# PB2_AdapterBoard_Rev0.net
KiCad netlist of a schematic drawn in Altium Designer
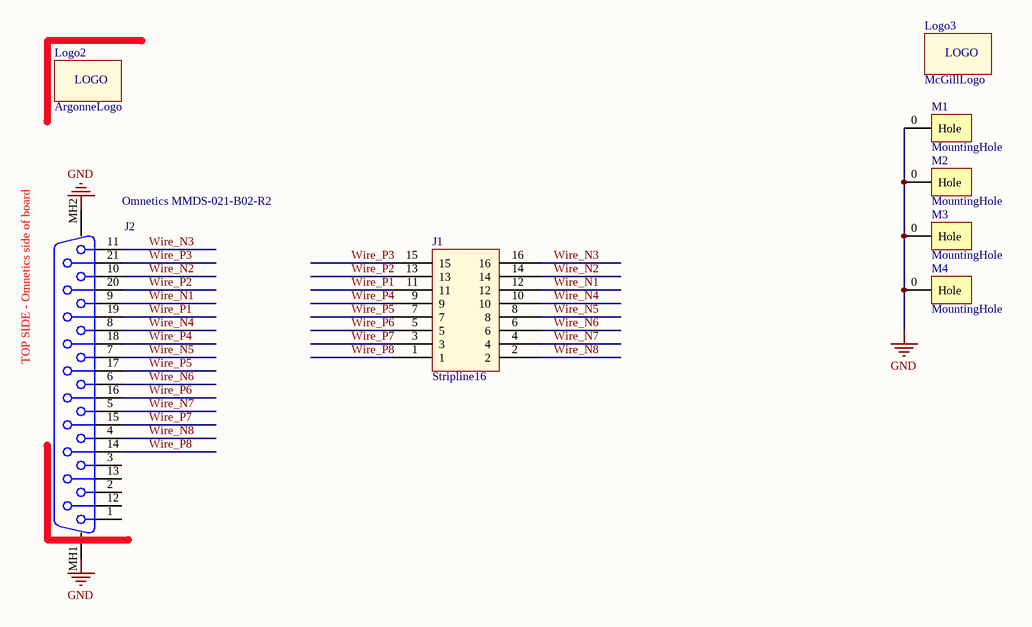
[diagram p0: PB2_AdapterBoard_Rev0.SchDoc]

(export (version "E")
  (design (tool "Eeschema 10.0.6"))
  (components
    (comp (ref "J1")
      (value "Stripline16")
      (footprint "Stripline16-HalfLength")
      (description "Stripline16 2mm x 15mm pads")
      (libsource (lib "SPT3G_AdapterBoard") (part "Stripline16"))
    )
    (comp (ref "J2")
      (value "Omnetics MMDS-021-B02-R2")
      (footprint "MMDS-021-B02-R2")
      (description "OmneticsMicroD21")
      (libsource (lib "SPT3G_LCBoard") (part "OmneticsMicroD21"))
    )
    (comp (ref "Logo2")
      (value "ArgonneLogo")
      (footprint "ArgonneLogo")
      (libsource (lib "SPT3G_AdapterBoard") (part "Logo"))
    )
    (comp (ref "Logo3")
      (value "McGillLogo")
      (footprint "McGillLogo1")
      (libsource (lib "SPT3G_AdapterBoard") (part "Logo"))
    )
    (comp (ref "M1")
      (value "MountingHole")
      (footprint "MountingHole")
      (libsource (lib "SPT3G_AdapterBoard") (part "MountingHole"))
    )
    (comp (ref "M2")
      (value "MountingHole")
      (footprint "MountingHole")
      (libsource (lib "SPT3G_AdapterBoard") (part "MountingHole"))
    )
    (comp (ref "M3")
      (value "MountingHole")
      (footprint "MountingHole")
      (libsource (lib "SPT3G_AdapterBoard") (part "MountingHole"))
    )
    (comp (ref "M4")
      (value "MountingHole")
      (footprint "MountingHole")
      (libsource (lib "SPT3G_AdapterBoard") (part "MountingHole"))
    )
  )
  (nets
    (net (code "1") (name "/Wire_N1") (class "Default")
      (node (ref "J1") (pin "12") (pinfunction "12_12") (pintype "passive"))
      (node (ref "J2") (pin "9") (pinfunction "9_9") (pintype "passive"))
    )
    (net (code "2") (name "/Wire_N2") (class "Default")
      (node (ref "J1") (pin "14") (pinfunction "14_14") (pintype "passive"))
      (node (ref "J2") (pin "10") (pinfunction "10_10") (pintype "passive"))
    )
    (net (code "3") (name "/Wire_N3") (class "Default")
      (node (ref "J1") (pin "16") (pinfunction "16_16") (pintype "passive"))
      (node (ref "J2") (pin "11") (pinfunction "11_11") (pintype "passive"))
    )
    (net (code "4") (name "/Wire_N4") (class "Default")
      (node (ref "J1") (pin "10") (pinfunction "10_10") (pintype "passive"))
      (node (ref "J2") (pin "8") (pinfunction "8_8") (pintype "passive"))
    )
    (net (code "5") (name "/Wire_N5") (class "Default")
      (node (ref "J1") (pin "8") (pinfunction "8_8") (pintype "passive"))
      (node (ref "J2") (pin "7") (pinfunction "7_7") (pintype "passive"))
    )
    (net (code "6") (name "/Wire_N6") (class "Default")
      (node (ref "J1") (pin "6") (pinfunction "6_6") (pintype "passive"))
      (node (ref "J2") (pin "6") (pinfunction "6_6") (pintype "passive"))
    )
    (net (code "7") (name "/Wire_N7") (class "Default")
      (node (ref "J1") (pin "4") (pinfunction "4_4") (pintype "passive"))
      (node (ref "J2") (pin "5") (pinfunction "5_5") (pintype "passive"))
    )
    (net (code "8") (name "/Wire_N8") (class "Default")
      (node (ref "J1") (pin "2") (pinfunction "2_2") (pintype "passive"))
      (node (ref "J2") (pin "4") (pinfunction "4_4") (pintype "passive"))
    )
    (net (code "9") (name "/Wire_P1") (class "Default")
      (node (ref "J1") (pin "11") (pinfunction "11_11") (pintype "passive"))
      (node (ref "J2") (pin "19") (pinfunction "19_19") (pintype "passive"))
    )
    (net (code "10") (name "/Wire_P2") (class "Default")
      (node (ref "J1") (pin "13") (pinfunction "13_13") (pintype "passive"))
      (node (ref "J2") (pin "20") (pinfunction "20_20") (pintype "passive"))
    )
    (net (code "11") (name "/Wire_P3") (class "Default")
      (node (ref "J1") (pin "15") (pinfunction "15_15") (pintype "passive"))
      (node (ref "J2") (pin "21") (pinfunction "21_21") (pintype "passive"))
    )
    (net (code "12") (name "/Wire_P4") (class "Default")
      (node (ref "J1") (pin "9") (pinfunction "9_9") (pintype "passive"))
      (node (ref "J2") (pin "18") (pinfunction "18_18") (pintype "passive"))
    )
    (net (code "13") (name "/Wire_P5") (class "Default")
      (node (ref "J1") (pin "7") (pinfunction "7_7") (pintype "passive"))
      (node (ref "J2") (pin "17") (pinfunction "17_17") (pintype "passive"))
    )
    (net (code "14") (name "/Wire_P6") (class "Default")
      (node (ref "J1") (pin "5") (pinfunction "5_5") (pintype "passive"))
      (node (ref "J2") (pin "16") (pinfunction "16_16") (pintype "passive"))
    )
    (net (code "15") (name "/Wire_P7") (class "Default")
      (node (ref "J1") (pin "3") (pinfunction "3_3") (pintype "passive"))
      (node (ref "J2") (pin "15") (pinfunction "15_15") (pintype "passive"))
    )
    (net (code "16") (name "/Wire_P8") (class "Default")
      (node (ref "J1") (pin "1") (pinfunction "1_1") (pintype "passive"))
      (node (ref "J2") (pin "14") (pinfunction "14_14") (pintype "passive"))
    )
    (net (code "17") (name "GND") (class "Default")
      (node (ref "J2") (pin "MH1") (pinfunction "MH1_MH1") (pintype "passive"))
      (node (ref "J2") (pin "MH2") (pinfunction "MH2_MH2") (pintype "passive"))
      (node (ref "M1") (pin "0") (pinfunction "Hole_0") (pintype "passive"))
      (node (ref "M2") (pin "0") (pinfunction "Hole_0") (pintype "passive"))
      (node (ref "M3") (pin "0") (pinfunction "Hole_0") (pintype "passive"))
      (node (ref "M4") (pin "0") (pinfunction "Hole_0") (pintype "passive"))
    )
    (net (code "18") (name "unconnected-(J2-Pad1)") (class "Default")
      (node (ref "J2") (pin "1") (pinfunction "1_1") (pintype "passive"))
    )
    (net (code "19") (name "unconnected-(J2-Pad2)") (class "Default")
      (node (ref "J2") (pin "2") (pinfunction "2_2") (pintype "passive"))
    )
    (net (code "20") (name "unconnected-(J2-Pad3)") (class "Default")
      (node (ref "J2") (pin "3") (pinfunction "3_3") (pintype "passive"))
    )
    (net (code "21") (name "unconnected-(J2-Pad12)") (class "Default")
      (node (ref "J2") (pin "12") (pinfunction "12_12") (pintype "passive"))
    )
    (net (code "22") (name "unconnected-(J2-Pad13)") (class "Default")
      (node (ref "J2") (pin "13") (pinfunction "13_13") (pintype "passive"))
    )
  )
)
